# LPCB234_-_24V_POWER.net
KiCad netlist of a schematic drawn in Altium Designer
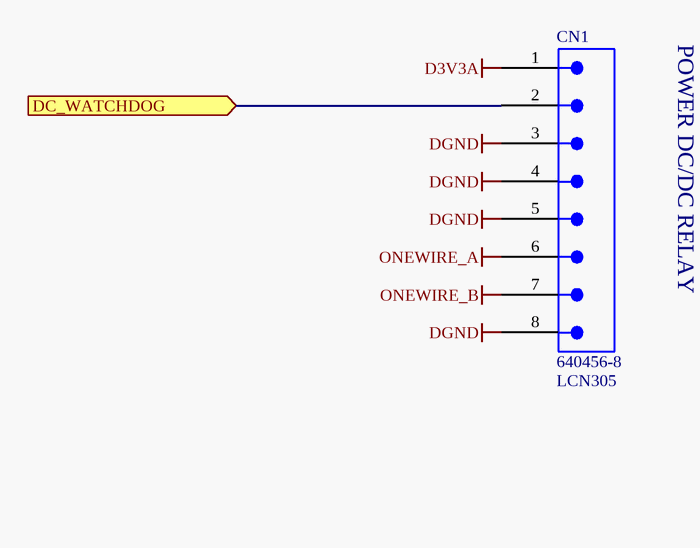
[diagram p0: LPCB234 - 24V POWER.SchDoc]

(export (version "E")
  (design (tool "Eeschema 10.0.6"))
  (components
    (comp (ref "CN1")
      (value "640456-8")
      (footprint "640456-8")
      (description "Connector, Male Header, 8 Way")
      (fields (field (name "LDL_NUMBER") "LCN305"))
      (libsource (lib "LDL_Connectors") (part "640456-8"))
    )
  )
  (nets
    (net (code "1") (name "/DC_WATCHDOG") (class "Default")
      (node (ref "CN1") (pin "2") (pinfunction "2_2") (pintype "passive"))
    )
    (net (code "2") (name "D3V3A") (class "Default")
      (node (ref "CN1") (pin "1") (pinfunction "1_1") (pintype "passive"))
    )
    (net (code "3") (name "DGND") (class "Default")
      (node (ref "CN1") (pin "3") (pinfunction "3_3") (pintype "passive"))
      (node (ref "CN1") (pin "4") (pinfunction "4_4") (pintype "passive"))
      (node (ref "CN1") (pin "5") (pinfunction "5_5") (pintype "passive"))
      (node (ref "CN1") (pin "8") (pinfunction "8_8") (pintype "passive"))
    )
    (net (code "4") (name "ONEWIRE_A") (class "Default")
      (node (ref "CN1") (pin "6") (pinfunction "6_6") (pintype "passive"))
    )
    (net (code "5") (name "ONEWIRE_B") (class "Default")
      (node (ref "CN1") (pin "7") (pinfunction "7_7") (pintype "passive"))
    )
  )
)
